# LTC6803.net
KiCad netlist of a schematic drawn in Altium Designer
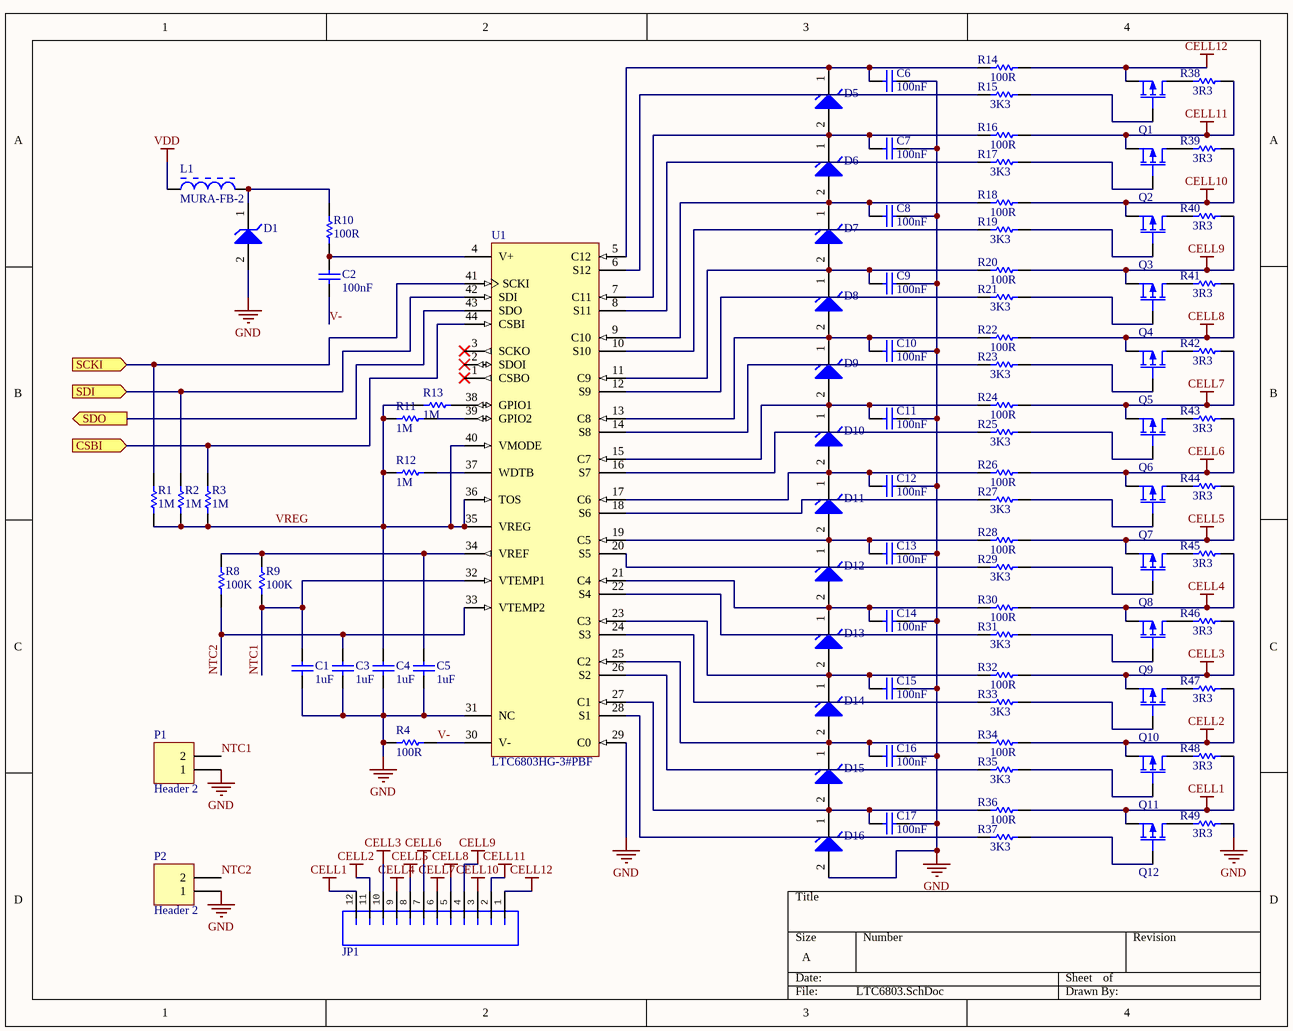
[diagram p0: LTC6803.SchDoc]

(export (version "E")
  (design (tool "Eeschema 10.0.6"))
  (components
    (comp (ref "C1")
      (value "1uF")
      (footprint "CAPC0603(1608)100_N")
      (description "CAP 1uF 6.3V Â±10% 0603 (1608 Metric) Thickness 1mm SMD")
      (fields (field (name "TOLERANCE") "Â±10%"))
      (libsource (lib "Altium Content Vault") (part "CAP"))
    )
    (comp (ref "C2")
      (value "100nF")
      (footprint "CAPC0603(1608)100_L")
      (description "CAP 100nF 100V Â±10% 0603 (1608 Metric) Thickness 1mm SMD")
      (fields (field (name "TOLERANCE") "Â±10%"))
      (libsource (lib "Altium Content Vault") (part "CAP"))
    )
    (comp (ref "C3")
      (value "1uF")
      (footprint "CAPC0603(1608)100_N")
      (description "CAP 1uF 6.3V Â±10% 0603 (1608 Metric) Thickness 1mm SMD")
      (fields (field (name "TOLERANCE") "Â±10%"))
      (libsource (lib "Altium Content Vault") (part "CAP"))
    )
    (comp (ref "C4")
      (value "1uF")
      (footprint "CAPC0603(1608)100_N")
      (description "CAP 1uF 6.3V Â±10% 0603 (1608 Metric) Thickness 1mm SMD")
      (fields (field (name "TOLERANCE") "Â±10%"))
      (libsource (lib "Altium Content Vault") (part "CAP"))
    )
    (comp (ref "C5")
      (value "1uF")
      (footprint "CAPC0603(1608)100_N")
      (description "CAP 1uF 6.3V Â±10% 0603 (1608 Metric) Thickness 1mm SMD")
      (fields (field (name "TOLERANCE") "Â±10%"))
      (libsource (lib "Altium Content Vault") (part "CAP"))
    )
    (comp (ref "C6")
      (value "100nF")
      (footprint "CAPC0603(1608)100_M")
      (description "CAP 100nF 6.3V Â±5% 0603 (1608 Metric) Thickness 1mm SMD")
      (fields (field (name "TOLERANCE") "Â±5%"))
      (libsource (lib "Altium Content Vault") (part "CAP"))
    )
    (comp (ref "C7")
      (value "100nF")
      (footprint "CAPC0603(1608)100_M")
      (description "CAP 100nF 6.3V Â±5% 0603 (1608 Metric) Thickness 1mm SMD")
      (fields (field (name "TOLERANCE") "Â±5%"))
      (libsource (lib "Altium Content Vault") (part "CAP"))
    )
    (comp (ref "C8")
      (value "100nF")
      (footprint "CAPC0603(1608)100_M")
      (description "CAP 100nF 6.3V Â±5% 0603 (1608 Metric) Thickness 1mm SMD")
      (fields (field (name "TOLERANCE") "Â±5%"))
      (libsource (lib "Altium Content Vault") (part "CAP"))
    )
    (comp (ref "C9")
      (value "100nF")
      (footprint "CAPC0603(1608)100_M")
      (description "CAP 100nF 6.3V Â±5% 0603 (1608 Metric) Thickness 1mm SMD")
      (fields (field (name "TOLERANCE") "Â±5%"))
      (libsource (lib "Altium Content Vault") (part "CAP"))
    )
    (comp (ref "C10")
      (value "100nF")
      (footprint "CAPC0603(1608)100_M")
      (description "CAP 100nF 6.3V Â±5% 0603 (1608 Metric) Thickness 1mm SMD")
      (fields (field (name "TOLERANCE") "Â±5%"))
      (libsource (lib "Altium Content Vault") (part "CAP"))
    )
    (comp (ref "C11")
      (value "100nF")
      (footprint "CAPC0603(1608)100_M")
      (description "CAP 100nF 6.3V Â±5% 0603 (1608 Metric) Thickness 1mm SMD")
      (fields (field (name "TOLERANCE") "Â±5%"))
      (libsource (lib "Altium Content Vault") (part "CAP"))
    )
    (comp (ref "C12")
      (value "100nF")
      (footprint "CAPC0603(1608)100_M")
      (description "CAP 100nF 6.3V Â±5% 0603 (1608 Metric) Thickness 1mm SMD")
      (fields (field (name "TOLERANCE") "Â±5%"))
      (libsource (lib "Altium Content Vault") (part "CAP"))
    )
    (comp (ref "C13")
      (value "100nF")
      (footprint "CAPC0603(1608)100_M")
      (description "CAP 100nF 6.3V Â±5% 0603 (1608 Metric) Thickness 1mm SMD")
      (fields (field (name "TOLERANCE") "Â±5%"))
      (libsource (lib "Altium Content Vault") (part "CAP"))
    )
    (comp (ref "C14")
      (value "100nF")
      (footprint "CAPC0603(1608)100_M")
      (description "CAP 100nF 6.3V Â±5% 0603 (1608 Metric) Thickness 1mm SMD")
      (fields (field (name "TOLERANCE") "Â±5%"))
      (libsource (lib "Altium Content Vault") (part "CAP"))
    )
    (comp (ref "C15")
      (value "100nF")
      (footprint "CAPC0603(1608)100_M")
      (description "CAP 100nF 6.3V Â±5% 0603 (1608 Metric) Thickness 1mm SMD")
      (fields (field (name "TOLERANCE") "Â±5%"))
      (libsource (lib "Altium Content Vault") (part "CAP"))
    )
    (comp (ref "C16")
      (value "100nF")
      (footprint "CAPC0603(1608)100_M")
      (description "CAP 100nF 6.3V Â±5% 0603 (1608 Metric) Thickness 1mm SMD")
      (fields (field (name "TOLERANCE") "Â±5%"))
      (libsource (lib "Altium Content Vault") (part "CAP"))
    )
    (comp (ref "C17")
      (value "100nF")
      (footprint "CAPC0603(1608)100_M")
      (description "CAP 100nF 6.3V Â±5% 0603 (1608 Metric) Thickness 1mm SMD")
      (fields (field (name "TOLERANCE") "Â±5%"))
      (libsource (lib "Altium Content Vault") (part "CAP"))
    )
    (comp (ref "D1") (value "~") (footprint "SOD-123") (libsource (lib "Components") (part "CMHZ5265B")))
    (comp (ref "D5")
      (value "~")
      (footprint "ONSC-SOD-323-2-477-02_V")
      (description "Zener Voltage Regulator, 300 mW, 2-Pin SOD-323, Tape and Reel")
      (fields (field (name "MANUFACTURER") "On Semiconductor") (field (name "PARTNUMBER") "MM3Z12VT1"))
      (libsource (lib "Altium Content Vault") (part "ONSC-K1A2-2"))
    )
    (comp (ref "D6")
      (value "~")
      (footprint "ONSC-SOD-323-2-477-02_V")
      (description "Zener Voltage Regulator, 300 mW, 2-Pin SOD-323, Tape and Reel")
      (fields (field (name "MANUFACTURER") "On Semiconductor") (field (name "PARTNUMBER") "MM3Z12VT1"))
      (libsource (lib "Altium Content Vault") (part "ONSC-K1A2-2"))
    )
    (comp (ref "D7")
      (value "~")
      (footprint "ONSC-SOD-323-2-477-02_V")
      (description "Zener Voltage Regulator, 300 mW, 2-Pin SOD-323, Tape and Reel")
      (fields (field (name "MANUFACTURER") "On Semiconductor") (field (name "PARTNUMBER") "MM3Z12VT1"))
      (libsource (lib "Altium Content Vault") (part "ONSC-K1A2-2"))
    )
    (comp (ref "D8")
      (value "~")
      (footprint "ONSC-SOD-323-2-477-02_V")
      (description "Zener Voltage Regulator, 300 mW, 2-Pin SOD-323, Tape and Reel")
      (fields (field (name "MANUFACTURER") "On Semiconductor") (field (name "PARTNUMBER") "MM3Z12VT1"))
      (libsource (lib "Altium Content Vault") (part "ONSC-K1A2-2"))
    )
    (comp (ref "D9")
      (value "~")
      (footprint "ONSC-SOD-323-2-477-02_V")
      (description "Zener Voltage Regulator, 300 mW, 2-Pin SOD-323, Tape and Reel")
      (fields (field (name "MANUFACTURER") "On Semiconductor") (field (name "PARTNUMBER") "MM3Z12VT1"))
      (libsource (lib "Altium Content Vault") (part "ONSC-K1A2-2"))
    )
    (comp (ref "D10")
      (value "~")
      (footprint "ONSC-SOD-323-2-477-02_V")
      (description "Zener Voltage Regulator, 300 mW, 2-Pin SOD-323, Tape and Reel")
      (fields (field (name "MANUFACTURER") "On Semiconductor") (field (name "PARTNUMBER") "MM3Z12VT1"))
      (libsource (lib "Altium Content Vault") (part "ONSC-K1A2-2"))
    )
    (comp (ref "D11")
      (value "~")
      (footprint "ONSC-SOD-323-2-477-02_V")
      (description "Zener Voltage Regulator, 300 mW, 2-Pin SOD-323, Tape and Reel")
      (fields (field (name "MANUFACTURER") "On Semiconductor") (field (name "PARTNUMBER") "MM3Z12VT1"))
      (libsource (lib "Altium Content Vault") (part "ONSC-K1A2-2"))
    )
    (comp (ref "D12")
      (value "~")
      (footprint "ONSC-SOD-323-2-477-02_V")
      (description "Zener Voltage Regulator, 300 mW, 2-Pin SOD-323, Tape and Reel")
      (fields (field (name "MANUFACTURER") "On Semiconductor") (field (name "PARTNUMBER") "MM3Z12VT1"))
      (libsource (lib "Altium Content Vault") (part "ONSC-K1A2-2"))
    )
    (comp (ref "D13")
      (value "~")
      (footprint "ONSC-SOD-323-2-477-02_V")
      (description "Zener Voltage Regulator, 300 mW, 2-Pin SOD-323, Tape and Reel")
      (fields (field (name "MANUFACTURER") "On Semiconductor") (field (name "PARTNUMBER") "MM3Z12VT1"))
      (libsource (lib "Altium Content Vault") (part "ONSC-K1A2-2"))
    )
    (comp (ref "D14")
      (value "~")
      (footprint "ONSC-SOD-323-2-477-02_V")
      (description "Zener Voltage Regulator, 300 mW, 2-Pin SOD-323, Tape and Reel")
      (fields (field (name "MANUFACTURER") "On Semiconductor") (field (name "PARTNUMBER") "MM3Z12VT1"))
      (libsource (lib "Altium Content Vault") (part "ONSC-K1A2-2"))
    )
    (comp (ref "D15")
      (value "~")
      (footprint "ONSC-SOD-323-2-477-02_V")
      (description "Zener Voltage Regulator, 300 mW, 2-Pin SOD-323, Tape and Reel")
      (fields (field (name "MANUFACTURER") "On Semiconductor") (field (name "PARTNUMBER") "MM3Z12VT1"))
      (libsource (lib "Altium Content Vault") (part "ONSC-K1A2-2"))
    )
    (comp (ref "D16")
      (value "~")
      (footprint "ONSC-SOD-323-2-477-02_V")
      (description "Zener Voltage Regulator, 300 mW, 2-Pin SOD-323, Tape and Reel")
      (fields (field (name "MANUFACTURER") "On Semiconductor") (field (name "PARTNUMBER") "MM3Z12VT1"))
      (libsource (lib "Altium Content Vault") (part "ONSC-K1A2-2"))
    )
    (comp (ref "JP1")
      (value "~")
      (footprint "JST-12-PTH")
      (libsource (lib "Components") (part "JST_12_RIGHT"))
    )
    (comp (ref "L1")
      (value "MURA-FB-2")
      (footprint "MURA-BLM31-B60-CHIP-2_V1")
      (libsource (lib "Components") (part "MURA-FB-2"))
    )
    (comp (ref "P1")
      (value "Header 2")
      (footprint "HDR1X2")
      (description "Header, 2-Pin")
      (fields (field (name "PUBLISHER") "Altium Limited"))
      (libsource (lib "Miscellaneous Connectors") (part "Header 2"))
    )
    (comp (ref "P2")
      (value "Header 2")
      (footprint "HDR1X2")
      (description "Header, 2-Pin")
      (fields (field (name "PUBLISHER") "Altium Limited"))
      (libsource (lib "Miscellaneous Connectors") (part "Header 2"))
    )
    (comp (ref "Q1")
      (value "MOSFET-P")
      (footprint "SOT23-3")
      (description "P-Channel MOSFET")
      (fields (field (name "PUBLISHER") "Altium Limited"))
      (libsource (lib "Components") (part "MOSFET-P"))
    )
    (comp (ref "Q2")
      (value "MOSFET-P")
      (footprint "SOT23-3")
      (description "P-Channel MOSFET")
      (fields (field (name "PUBLISHER") "Altium Limited"))
      (libsource (lib "Components") (part "MOSFET-P"))
    )
    (comp (ref "Q3")
      (value "MOSFET-P")
      (footprint "SOT23-3")
      (description "P-Channel MOSFET")
      (fields (field (name "PUBLISHER") "Altium Limited"))
      (libsource (lib "Components") (part "MOSFET-P"))
    )
    (comp (ref "Q4")
      (value "MOSFET-P")
      (footprint "SOT23-3")
      (description "P-Channel MOSFET")
      (fields (field (name "PUBLISHER") "Altium Limited"))
      (libsource (lib "Components") (part "MOSFET-P"))
    )
    (comp (ref "Q5")
      (value "MOSFET-P")
      (footprint "SOT23-3")
      (description "P-Channel MOSFET")
      (fields (field (name "PUBLISHER") "Altium Limited"))
      (libsource (lib "Components") (part "MOSFET-P"))
    )
    (comp (ref "Q6")
      (value "MOSFET-P")
      (footprint "SOT23-3")
      (description "P-Channel MOSFET")
      (fields (field (name "PUBLISHER") "Altium Limited"))
      (libsource (lib "Components") (part "MOSFET-P"))
    )
    (comp (ref "Q7")
      (value "MOSFET-P")
      (footprint "SOT23-3")
      (description "P-Channel MOSFET")
      (fields (field (name "PUBLISHER") "Altium Limited"))
      (libsource (lib "Components") (part "MOSFET-P"))
    )
    (comp (ref "Q8")
      (value "MOSFET-P")
      (footprint "SOT23-3")
      (description "P-Channel MOSFET")
      (fields (field (name "PUBLISHER") "Altium Limited"))
      (libsource (lib "Components") (part "MOSFET-P"))
    )
    (comp (ref "Q9")
      (value "MOSFET-P")
      (footprint "SOT23-3")
      (description "P-Channel MOSFET")
      (fields (field (name "PUBLISHER") "Altium Limited"))
      (libsource (lib "Components") (part "MOSFET-P"))
    )
    (comp (ref "Q10")
      (value "MOSFET-P")
      (footprint "SOT23-3")
      (description "P-Channel MOSFET")
      (fields (field (name "PUBLISHER") "Altium Limited"))
      (libsource (lib "Components") (part "MOSFET-P"))
    )
    (comp (ref "Q11")
      (value "MOSFET-P")
      (footprint "SOT23-3")
      (description "P-Channel MOSFET")
      (fields (field (name "PUBLISHER") "Altium Limited"))
      (libsource (lib "Components") (part "MOSFET-P"))
    )
    (comp (ref "Q12")
      (value "MOSFET-P")
      (footprint "SOT23-3")
      (description "P-Channel MOSFET")
      (fields (field (name "PUBLISHER") "Altium Limited"))
      (libsource (lib "Components") (part "MOSFET-P"))
    )
    (comp (ref "R1")
      (value "1M")
      (footprint "RESC0603(1608)_L")
      (description "1M 0.1W 1% 0603 (1608 Metric)  SMD")
      (fields (field (name "POWER") "0.1 W") (field (name "TOLERANCE") "1 %"))
      (libsource (lib "Altium Content Vault") (part "RES"))
    )
    (comp (ref "R2")
      (value "1M")
      (footprint "RESC0603(1608)_L")
      (description "1M 0.1W 1% 0603 (1608 Metric)  SMD")
      (fields (field (name "POWER") "0.1 W") (field (name "TOLERANCE") "1 %"))
      (libsource (lib "Altium Content Vault") (part "RES"))
    )
    (comp (ref "R3")
      (value "1M")
      (footprint "RESC0603(1608)_L")
      (description "1M 0.1W 1% 0603 (1608 Metric)  SMD")
      (fields (field (name "POWER") "0.1 W") (field (name "TOLERANCE") "1 %"))
      (libsource (lib "Altium Content Vault") (part "RES"))
    )
    (comp (ref "R4")
      (value "100R")
      (footprint "RESC0603(1608)_L")
      (description "100R 0.1W 5% 0603 (1608 Metric)  SMD")
      (fields (field (name "TOLERANCE") "5 %") (field (name "POWER") "0.1 W"))
      (libsource (lib "Altium Content Vault") (part "RES"))
    )
    (comp (ref "R8")
      (value "100K")
      (footprint "RESC0603(1608)_N")
      (description "100K 0.1W 5% 0603 (1608 Metric)  SMD")
      (fields (field (name "TOLERANCE") "5 %") (field (name "POWER") "0.1 W"))
      (libsource (lib "Altium Content Vault") (part "RES"))
    )
    (comp (ref "R9")
      (value "100K")
      (footprint "RESC0603(1608)_N")
      (description "100K 0.1W 5% 0603 (1608 Metric)  SMD")
      (fields (field (name "TOLERANCE") "5 %") (field (name "POWER") "0.1 W"))
      (libsource (lib "Altium Content Vault") (part "RES"))
    )
    (comp (ref "R10")
      (value "100R")
      (footprint "RESC0603(1608)_L")
      (description "100R 0.1W 5% 0603 (1608 Metric)  SMD")
      (fields (field (name "TOLERANCE") "5 %") (field (name "POWER") "0.1 W"))
      (libsource (lib "Altium Content Vault") (part "CMP-1012-00050-1"))
    )
    (comp (ref "R11")
      (value "1M")
      (footprint "RESC0603(1608)_L")
      (description "1M 0.1W 1% 0603 (1608 Metric)  SMD")
      (fields (field (name "POWER") "0.1 W") (field (name "TOLERANCE") "1 %"))
      (libsource (lib "Altium Content Vault") (part "RES"))
    )
    (comp (ref "R12")
      (value "1M")
      (footprint "RESC0603(1608)_L")
      (description "1M 0.1W 1% 0603 (1608 Metric)  SMD")
      (fields (field (name "POWER") "0.1 W") (field (name "TOLERANCE") "1 %"))
      (libsource (lib "Altium Content Vault") (part "RES"))
    )
    (comp (ref "R13")
      (value "1M")
      (footprint "RESC0603(1608)_L")
      (description "1M 0.1W 1% 0603 (1608 Metric)  SMD")
      (fields (field (name "POWER") "0.1 W") (field (name "TOLERANCE") "1 %"))
      (libsource (lib "Altium Content Vault") (part "RES"))
    )
    (comp (ref "R14")
      (value "100R")
      (footprint "RESC0603(1608)_N")
      (description "100R 0.1W 5% 0603 (1608 Metric)  SMD")
      (fields (field (name "TOLERANCE") "5 %") (field (name "POWER") "0.1 W"))
      (libsource (lib "Altium Content Vault") (part "CMP-1012-00050-1"))
    )
    (comp (ref "R15")
      (value "3K3")
      (footprint "RESC0603(1608)_N")
      (description "3K3 0.1W 5% 0603 (1608 Metric)  SMD")
      (fields (field (name "TOLERANCE") "5 %") (field (name "POWER") "0.1 W"))
      (libsource (lib "Altium Content Vault") (part "RES"))
    )
    (comp (ref "R16")
      (value "100R")
      (footprint "RESC0603(1608)_N")
      (description "100R 0.1W 5% 0603 (1608 Metric)  SMD")
      (fields (field (name "TOLERANCE") "5 %") (field (name "POWER") "0.1 W"))
      (libsource (lib "Altium Content Vault") (part "CMP-1012-00050-1"))
    )
    (comp (ref "R17")
      (value "3K3")
      (footprint "RESC0603(1608)_N")
      (description "3K3 0.1W 5% 0603 (1608 Metric)  SMD")
      (fields (field (name "TOLERANCE") "5 %") (field (name "POWER") "0.1 W"))
      (libsource (lib "Altium Content Vault") (part "RES"))
    )
    (comp (ref "R18")
      (value "100R")
      (footprint "RESC0603(1608)_N")
      (description "100R 0.1W 5% 0603 (1608 Metric)  SMD")
      (fields (field (name "TOLERANCE") "5 %") (field (name "POWER") "0.1 W"))
      (libsource (lib "Altium Content Vault") (part "CMP-1012-00050-1"))
    )
    (comp (ref "R19")
      (value "3K3")
      (footprint "RESC0603(1608)_N")
      (description "3K3 0.1W 5% 0603 (1608 Metric)  SMD")
      (fields (field (name "TOLERANCE") "5 %") (field (name "POWER") "0.1 W"))
      (libsource (lib "Altium Content Vault") (part "RES"))
    )
    (comp (ref "R20")
      (value "100R")
      (footprint "RESC0603(1608)_N")
      (description "100R 0.1W 5% 0603 (1608 Metric)  SMD")
      (fields (field (name "TOLERANCE") "5 %") (field (name "POWER") "0.1 W"))
      (libsource (lib "Altium Content Vault") (part "CMP-1012-00050-1"))
    )
    (comp (ref "R21")
      (value "3K3")
      (footprint "RESC0603(1608)_N")
      (description "3K3 0.1W 5% 0603 (1608 Metric)  SMD")
      (fields (field (name "TOLERANCE") "5 %") (field (name "POWER") "0.1 W"))
      (libsource (lib "Altium Content Vault") (part "RES"))
    )
    (comp (ref "R22")
      (value "100R")
      (footprint "RESC0603(1608)_N")
      (description "100R 0.1W 5% 0603 (1608 Metric)  SMD")
      (fields (field (name "TOLERANCE") "5 %") (field (name "POWER") "0.1 W"))
      (libsource (lib "Altium Content Vault") (part "CMP-1012-00050-1"))
    )
    (comp (ref "R23")
      (value "3K3")
      (footprint "RESC0603(1608)_N")
      (description "3K3 0.1W 5% 0603 (1608 Metric)  SMD")
      (fields (field (name "TOLERANCE") "5 %") (field (name "POWER") "0.1 W"))
      (libsource (lib "Altium Content Vault") (part "RES"))
    )
    (comp (ref "R24")
      (value "100R")
      (footprint "RESC0603(1608)_N")
      (description "100R 0.1W 5% 0603 (1608 Metric)  SMD")
      (fields (field (name "TOLERANCE") "5 %") (field (name "POWER") "0.1 W"))
      (libsource (lib "Altium Content Vault") (part "CMP-1012-00050-1"))
    )
    (comp (ref "R25")
      (value "3K3")
      (footprint "RESC0603(1608)_N")
      (description "3K3 0.1W 5% 0603 (1608 Metric)  SMD")
      (fields (field (name "TOLERANCE") "5 %") (field (name "POWER") "0.1 W"))
      (libsource (lib "Altium Content Vault") (part "RES"))
    )
    (comp (ref "R26")
      (value "100R")
      (footprint "RESC0603(1608)_N")
      (description "100R 0.1W 5% 0603 (1608 Metric)  SMD")
      (fields (field (name "TOLERANCE") "5 %") (field (name "POWER") "0.1 W"))
      (libsource (lib "Altium Content Vault") (part "CMP-1012-00050-1"))
    )
    (comp (ref "R27")
      (value "3K3")
      (footprint "RESC0603(1608)_N")
      (description "3K3 0.1W 5% 0603 (1608 Metric)  SMD")
      (fields (field (name "TOLERANCE") "5 %") (field (name "POWER") "0.1 W"))
      (libsource (lib "Altium Content Vault") (part "RES"))
    )
    (comp (ref "R28")
      (value "100R")
      (footprint "RESC0603(1608)_N")
      (description "100R 0.1W 5% 0603 (1608 Metric)  SMD")
      (fields (field (name "TOLERANCE") "5 %") (field (name "POWER") "0.1 W"))
      (libsource (lib "Altium Content Vault") (part "CMP-1012-00050-1"))
    )
    (comp (ref "R29")
      (value "3K3")
      (footprint "RESC0603(1608)_N")
      (description "3K3 0.1W 5% 0603 (1608 Metric)  SMD")
      (fields (field (name "TOLERANCE") "5 %") (field (name "POWER") "0.1 W"))
      (libsource (lib "Altium Content Vault") (part "RES"))
    )
    (comp (ref "R30")
      (value "100R")
      (footprint "RESC0603(1608)_N")
      (description "100R 0.1W 5% 0603 (1608 Metric)  SMD")
      (fields (field (name "TOLERANCE") "5 %") (field (name "POWER") "0.1 W"))
      (libsource (lib "Altium Content Vault") (part "CMP-1012-00050-1"))
    )
    (comp (ref "R31")
      (value "3K3")
      (footprint "RESC0603(1608)_N")
      (description "3K3 0.1W 5% 0603 (1608 Metric)  SMD")
      (fields (field (name "TOLERANCE") "5 %") (field (name "POWER") "0.1 W"))
      (libsource (lib "Altium Content Vault") (part "RES"))
    )
    (comp (ref "R32")
      (value "100R")
      (footprint "RESC0603(1608)_N")
      (description "100R 0.1W 5% 0603 (1608 Metric)  SMD")
      (fields (field (name "TOLERANCE") "5 %") (field (name "POWER") "0.1 W"))
      (libsource (lib "Altium Content Vault") (part "CMP-1012-00050-1"))
    )
    (comp (ref "R33")
      (value "3K3")
      (footprint "RESC0603(1608)_N")
      (description "3K3 0.1W 5% 0603 (1608 Metric)  SMD")
      (fields (field (name "TOLERANCE") "5 %") (field (name "POWER") "0.1 W"))
      (libsource (lib "Altium Content Vault") (part "RES"))
    )
    (comp (ref "R34")
      (value "100R")
      (footprint "RESC0603(1608)_N")
      (description "100R 0.1W 5% 0603 (1608 Metric)  SMD")
      (fields (field (name "TOLERANCE") "5 %") (field (name "POWER") "0.1 W"))
      (libsource (lib "Altium Content Vault") (part "CMP-1012-00050-1"))
    )
    (comp (ref "R35")
      (value "3K3")
      (footprint "RESC0603(1608)_N")
      (description "3K3 0.1W 5% 0603 (1608 Metric)  SMD")
      (fields (field (name "TOLERANCE") "5 %") (field (name "POWER") "0.1 W"))
      (libsource (lib "Altium Content Vault") (part "RES"))
    )
    (comp (ref "R36")
      (value "100R")
      (footprint "RESC0603(1608)_N")
      (description "100R 0.1W 5% 0603 (1608 Metric)  SMD")
      (fields (field (name "TOLERANCE") "5 %") (field (name "POWER") "0.1 W"))
      (libsource (lib "Altium Content Vault") (part "CMP-1012-00050-1"))
    )
    (comp (ref "R37")
      (value "3K3")
      (footprint "RESC0603(1608)_N")
      (description "3K3 0.1W 5% 0603 (1608 Metric)  SMD")
      (fields (field (name "TOLERANCE") "5 %") (field (name "POWER") "0.1 W"))
      (libsource (lib "Altium Content Vault") (part "RES"))
    )
    (comp (ref "R38")
      (value "3R3")
      (footprint "RESC2512(6432)_N")
      (description "3R3 1W 5% 2512 (6432 Metric)  SMD")
      (fields (field (name "TOLERANCE") "5 %") (field (name "POWER") "1 W"))
      (libsource (lib "Altium Content Vault") (part "RES"))
    )
    (comp (ref "R39")
      (value "3R3")
      (footprint "RESC2512(6432)_N")
      (description "3R3 1W 5% 2512 (6432 Metric)  SMD")
      (fields (field (name "TOLERANCE") "5 %") (field (name "POWER") "1 W"))
      (libsource (lib "Altium Content Vault") (part "RES"))
    )
    (comp (ref "R40")
      (value "3R3")
      (footprint "RESC2512(6432)_N")
      (description "3R3 1W 5% 2512 (6432 Metric)  SMD")
      (fields (field (name "TOLERANCE") "5 %") (field (name "POWER") "1 W"))
      (libsource (lib "Altium Content Vault") (part "RES"))
    )
    (comp (ref "R41")
      (value "3R3")
      (footprint "RESC2512(6432)_N")
      (description "3R3 1W 5% 2512 (6432 Metric)  SMD")
      (fields (field (name "TOLERANCE") "5 %") (field (name "POWER") "1 W"))
      (libsource (lib "Altium Content Vault") (part "RES"))
    )
    (comp (ref "R42")
      (value "3R3")
      (footprint "RESC2512(6432)_N")
      (description "3R3 1W 5% 2512 (6432 Metric)  SMD")
      (fields (field (name "TOLERANCE") "5 %") (field (name "POWER") "1 W"))
      (libsource (lib "Altium Content Vault") (part "RES"))
    )
    (comp (ref "R43")
      (value "3R3")
      (footprint "RESC2512(6432)_N")
      (description "3R3 1W 5% 2512 (6432 Metric)  SMD")
      (fields (field (name "TOLERANCE") "5 %") (field (name "POWER") "1 W"))
      (libsource (lib "Altium Content Vault") (part "RES"))
    )
    (comp (ref "R44")
      (value "3R3")
      (footprint "RESC2512(6432)_N")
      (description "3R3 1W 5% 2512 (6432 Metric)  SMD")
      (fields (field (name "TOLERANCE") "5 %") (field (name "POWER") "1 W"))
      (libsource (lib "Altium Content Vault") (part "RES"))
    )
    (comp (ref "R45")
      (value "3R3")
      (footprint "RESC2512(6432)_N")
      (description "3R3 1W 5% 2512 (6432 Metric)  SMD")
      (fields (field (name "TOLERANCE") "5 %") (field (name "POWER") "1 W"))
      (libsource (lib "Altium Content Vault") (part "RES"))
    )
    (comp (ref "R46")
      (value "3R3")
      (footprint "RESC2512(6432)_N")
      (description "3R3 1W 5% 2512 (6432 Metric)  SMD")
      (fields (field (name "TOLERANCE") "5 %") (field (name "POWER") "1 W"))
      (libsource (lib "Altium Content Vault") (part "RES"))
    )
    (comp (ref "R47")
      (value "3R3")
      (footprint "RESC2512(6432)_N")
      (description "3R3 1W 5% 2512 (6432 Metric)  SMD")
      (fields (field (name "TOLERANCE") "5 %") (field (name "POWER") "1 W"))
      (libsource (lib "Altium Content Vault") (part "RES"))
    )
    (comp (ref "R48")
      (value "3R3")
      (footprint "RESC2512(6432)_N")
      (description "3R3 1W 5% 2512 (6432 Metric)  SMD")
      (fields (field (name "TOLERANCE") "5 %") (field (name "POWER") "1 W"))
      (libsource (lib "Altium Content Vault") (part "RES"))
    )
    (comp (ref "R49")
      (value "3R3")
      (footprint "RESC2512(6432)_N")
      (description "3R3 1W 5% 2512 (6432 Metric)  SMD")
      (fields (field (name "TOLERANCE") "5 %") (field (name "POWER") "1 W"))
      (libsource (lib "Altium Content Vault") (part "RES"))
    )
    (comp (ref "U1")
      (value "LTC6803HG-3#PBF")
      (footprint "LT-G-44_L")
      (description "Multicell Battery Stack Monitor, 60 V Vin MAX, 44-pin SOP (G-44), -40 to 125 degC, Pb-Free")
      (fields (field (name "MANUFACTURER") "Linear Technology"))
      (libsource (lib "Altium Content Vault") (part "LT-LTC6803-3-G-44"))
    )
  )
  (nets
    (net (code "1") (name "/CSBI") (class "Default")
      (node (ref "R3") (pin "2") (pinfunction "2_2") (pintype "passive"))
      (node (ref "U1") (pin "44") (pinfunction "CSBI_44") (pintype "input"))
    )
    (net (code "2") (name "/NTC1") (class "Default")
      (node (ref "C1") (pin "2") (pinfunction "2_2") (pintype "passive"))
      (node (ref "P1") (pin "2") (pinfunction "2_2") (pintype "passive"))
      (node (ref "R9") (pin "1") (pinfunction "1_1") (pintype "passive"))
      (node (ref "U1") (pin "32") (pinfunction "VTEMP1_32") (pintype "input"))
    )
    (net (code "3") (name "/NTC2") (class "Default")
      (node (ref "C3") (pin "2") (pinfunction "2_2") (pintype "passive"))
      (node (ref "P2") (pin "2") (pinfunction "2_2") (pintype "passive"))
      (node (ref "R8") (pin "1") (pinfunction "1_1") (pintype "passive"))
      (node (ref "U1") (pin "33") (pinfunction "VTEMP2_33") (pintype "input"))
    )
    (net (code "4") (name "/SCKI") (class "Default")
      (node (ref "R1") (pin "2") (pinfunction "2_2") (pintype "passive"))
      (node (ref "U1") (pin "41") (pinfunction "SCKI_41") (pintype "input"))
    )
    (net (code "5") (name "/SDI") (class "Default")
      (node (ref "R2") (pin "2") (pinfunction "2_2") (pintype "passive"))
      (node (ref "U1") (pin "42") (pinfunction "SDI_42") (pintype "input"))
    )
    (net (code "6") (name "/SDO") (class "Default")
      (node (ref "U1") (pin "43") (pinfunction "SDO_43") (pintype "open_collector"))
    )
    (net (code "7") (name "/V-") (class "Default")
      (node (ref "C2") (pin "1") (pinfunction "1_1") (pintype "passive"))
      (node (ref "R4") (pin "2") (pinfunction "2_2") (pintype "passive"))
      (node (ref "U1") (pin "30") (pinfunction "V-_30") (pintype "power_in"))
    )
    (net (code "8") (name "/VREG") (class "Default")
      (node (ref "C4") (pin "2") (pinfunction "2_2") (pintype "passive"))
      (node (ref "R1") (pin "1") (pinfunction "1_1") (pintype "passive"))
      (node (ref "R11") (pin "1") (pinfunction "1_1") (pintype "passive"))
      (node (ref "R12") (pin "1") (pinfunction "1_1") (pintype "passive"))
      (node (ref "R13") (pin "1") (pinfunction "1_1") (pintype "passive"))
      (node (ref "R2") (pin "1") (pinfunction "1_1") (pintype "passive"))
      (node (ref "R3") (pin "1") (pinfunction "1_1") (pintype "passive"))
      (node (ref "U1") (pin "35") (pinfunction "VREG_35") (pintype "power_in"))
      (node (ref "U1") (pin "36") (pinfunction "TOS_36") (pintype "input"))
      (node (ref "U1") (pin "40") (pinfunction "VMODE_40") (pintype "input"))
    )
    (net (code "9") (name "CELL1") (class "Default")
      (node (ref "JP1") (pin "12") (pinfunction "12_12") (pintype "passive"))
      (node (ref "Q12") (pin "3") (pinfunction "S_3") (pintype "passive"))
      (node (ref "R36") (pin "2") (pinfunction "2_2") (pintype "passive"))
      (node (ref "R48") (pin "1") (pinfunction "1_1") (pintype "passive"))
    )
    (net (code "10") (name "CELL2") (class "Default")
      (node (ref "JP1") (pin "11") (pinfunction "11_11") (pintype "passive"))
      (node (ref "Q11") (pin "3") (pinfunction "S_3") (pintype "passive"))
      (node (ref "R34") (pin "2") (pinfunction "2_2") (pintype "passive"))
      (node (ref "R47") (pin "1") (pinfunction "1_1") (pintype "passive"))
    )
    (net (code "11") (name "CELL3") (class "Default")
      (node (ref "JP1") (pin "10") (pinfunction "10_10") (pintype "passive"))
      (node (ref "Q10") (pin "3") (pinfunction "S_3") (pintype "passive"))
      (node (ref "R32") (pin "2") (pinfunction "2_2") (pintype "passive"))
      (node (ref "R46") (pin "1") (pinfunction "1_1") (pintype "passive"))
    )
    (net (code "12") (name "CELL4") (class "Default")
      (node (ref "JP1") (pin "9") (pinfunction "9_9") (pintype "passive"))
      (node (ref "Q9") (pin "3") (pinfunction "S_3") (pintype "passive"))
      (node (ref "R30") (pin "2") (pinfunction "2_2") (pintype "passive"))
      (node (ref "R45") (pin "1") (pinfunction "1_1") (pintype "passive"))
    )
    (net (code "13") (name "CELL5") (class "Default")
      (node (ref "JP1") (pin "8") (pinfunction "8_8") (pintype "passive"))
      (node (ref "Q8") (pin "3") (pinfunction "S_3") (pintype "passive"))
      (node (ref "R28") (pin "2") (pinfunction "2_2") (pintype "passive"))
      (node (ref "R44") (pin "1") (pinfunction "1_1") (pintype "passive"))
    )
    (net (code "14") (name "CELL6") (class "Default")
      (node (ref "JP1") (pin "7") (pinfunction "7_7") (pintype "passive"))
      (node (ref "Q7") (pin "3") (pinfunction "S_3") (pintype "passive"))
      (node (ref "R26") (pin "2") (pinfunction "2_2") (pintype "passive"))
      (node (ref "R43") (pin "1") (pinfunction "1_1") (pintype "passive"))
    )
    (net (code "15") (name "CELL7") (class "Default")
      (node (ref "JP1") (pin "6") (pinfunction "6_6") (pintype "passive"))
      (node (ref "Q6") (pin "3") (pinfunction "S_3") (pintype "passive"))
      (node (ref "R24") (pin "2") (pinfunction "2_2") (pintype "passive"))
      (node (ref "R42") (pin "1") (pinfunction "1_1") (pintype "passive"))
    )
    (net (code "16") (name "CELL8") (class "Default")
      (node (ref "JP1") (pin "5") (pinfunction "5_5") (pintype "passive"))
      (node (ref "Q5") (pin "3") (pinfunction "S_3") (pintype "passive"))
      (node (ref "R22") (pin "2") (pinfunction "2_2") (pintype "passive"))
      (node (ref "R41") (pin "1") (pinfunction "1_1") (pintype "passive"))
    )
    (net (code "17") (name "CELL9") (class "Default")
      (node (ref "JP1") (pin "4") (pinfunction "4_4") (pintype "passive"))
      (node (ref "Q4") (pin "3") (pinfunction "S_3") (pintype "passive"))
      (node (ref "R20") (pin "2") (pinfunction "2_2") (pintype "passive"))
      (node (ref "R40") (pin "1") (pinfunction "1_1") (pintype "passive"))
    )
    (net (code "18") (name "CELL10") (class "Default")
      (node (ref "JP1") (pin "3") (pinfunction "3_3") (pintype "passive"))
      (node (ref "Q3") (pin "3") (pinfunction "S_3") (pintype "passive"))
      (node (ref "R18") (pin "2") (pinfunction "2_2") (pintype "passive"))
      (node (ref "R39") (pin "1") (pinfunction "1_1") (pintype "passive"))
    )
    (net (code "19") (name "CELL11") (class "Default")
      (node (ref "JP1") (pin "2") (pinfunction "2_2") (pintype "passive"))
      (node (ref "Q2") (pin "3") (pinfunction "S_3") (pintype "passive"))
      (node (ref "R16") (pin "2") (pinfunction "2_2") (pintype "passive"))
      (node (ref "R38") (pin "1") (pinfunction "1_1") (pintype "passive"))
    )
    (net (code "20") (name "CELL12") (class "Default")
      (node (ref "JP1") (pin "1") (pinfunction "1_1") (pintype "passive"))
      (node (ref "Q1") (pin "3") (pinfunction "S_3") (pintype "passive"))
      (node (ref "R14") (pin "2") (pinfunction "2_2") (pintype "passive"))
    )
    (net (code "21") (name "GND") (class "Default")
      (node (ref "C1") (pin "1") (pinfunction "1_1") (pintype "passive"))
      (node (ref "C10") (pin "1") (pinfunction "1_1") (pintype "passive"))
      (node (ref "C11") (pin "1") (pinfunction "1_1") (pintype "passive"))
      (node (ref "C12") (pin "1") (pinfunction "1_1") (pintype "passive"))
      (node (ref "C13") (pin "1") (pinfunction "1_1") (pintype "passive"))
      (node (ref "C14") (pin "1") (pinfunction "1_1") (pintype "passive"))
      (node (ref "C15") (pin "1") (pinfunction "1_1") (pintype "passive"))
      (node (ref "C16") (pin "1") (pinfunction "1_1") (pintype "passive"))
      (node (ref "C17") (pin "1") (pinfunction "1_1") (pintype "passive"))
      (node (ref "C3") (pin "1") (pinfunction "1_1") (pintype "passive"))
      (node (ref "C4") (pin "1") (pinfunction "1_1") (pintype "passive"))
      (node (ref "C5") (pin "1") (pinfunction "1_1") (pintype "passive"))
      (node (ref "C6") (pin "1") (pinfunction "1_1") (pintype "passive"))
      (node (ref "C7") (pin "1") (pinfunction "1_1") (pintype "passive"))
      (node (ref "C8") (pin "1") (pinfunction "1_1") (pintype "passive"))
      (node (ref "C9") (pin "1") (pinfunction "1_1") (pintype "passive"))
      (node (ref "D1") (pin "2") (pinfunction "A_2") (pintype "passive"))
      (node (ref "D16") (pin "2") (pinfunction "A_2") (pintype "passive"))
      (node (ref "P1") (pin "1") (pinfunction "1_1") (pintype "passive"))
      (node (ref "P2") (pin "1") (pinfunction "1_1") (pintype "passive"))
      (node (ref "R4") (pin "1") (pinfunction "1_1") (pintype "passive"))
      (node (ref "R49") (pin "1") (pinfunction "1_1") (pintype "passive"))
      (node (ref "U1") (pin "29") (pinfunction "C0_29") (pintype "input"))
      (node (ref "U1") (pin "31") (pinfunction "NC_31") (pintype "passive"))
    )
    (net (code "22") (name "Net-(D1-K)") (class "Default")
      (node (ref "D1") (pin "1") (pinfunction "K_1") (pintype "passive"))
      (node (ref "L1") (pin "2") (pinfunction "2_2") (pintype "passive"))
      (node (ref "R10") (pin "2") (pinfunction "2_2") (pintype "passive"))
    )
    (net (code "23") (name "Net-(D5-A)") (class "Default")
      (node (ref "C7") (pin "2") (pinfunction "2_2") (pintype "passive"))
      (node (ref "D5") (pin "2") (pinfunction "A_2") (pintype "passive"))
      (node (ref "D6") (pin "1") (pinfunction "K_1") (pintype "passive"))
      (node (ref "R16") (pin "1") (pinfunction "1_1") (pintype "passive"))
      (node (ref "U1") (pin "7") (pinfunction "C11_7") (pintype "input"))
    )
    (net (code "24") (name "Net-(D5-K)") (class "Default")
      (node (ref "C6") (pin "2") (pinfunction "2_2") (pintype "passive"))
      (node (ref "D5") (pin "1") (pinfunction "K_1") (pintype "passive"))
      (node (ref "R14") (pin "1") (pinfunction "1_1") (pintype "passive"))
      (node (ref "U1") (pin "5") (pinfunction "C12_5") (pintype "input"))
    )
    (net (code "25") (name "Net-(D6-A)") (class "Default")
      (node (ref "C8") (pin "2") (pinfunction "2_2") (pintype "passive"))
      (node (ref "D6") (pin "2") (pinfunction "A_2") (pintype "passive"))
      (node (ref "D7") (pin "1") (pinfunction "K_1") (pintype "passive"))
      (node (ref "R18") (pin "1") (pinfunction "1_1") (pintype "passive"))
      (node (ref "U1") (pin "9") (pinfunction "C10_9") (pintype "input"))
    )
    (net (code "26") (name "Net-(D7-A)") (class "Default")
      (node (ref "C9") (pin "2") (pinfunction "2_2") (pintype "passive"))
      (node (ref "D7") (pin "2") (pinfunction "A_2") (pintype "passive"))
      (node (ref "D8") (pin "1") (pinfunction "K_1") (pintype "passive"))
      (node (ref "R20") (pin "1") (pinfunction "1_1") (pintype "passive"))
      (node (ref "U1") (pin "11") (pinfunction "C9_11") (pintype "input"))
    )
    (net (code "27") (name "Net-(D8-A)") (class "Default")
      (node (ref "C10") (pin "2") (pinfunction "2_2") (pintype "passive"))
      (node (ref "D8") (pin "2") (pinfunction "A_2") (pintype "passive"))
      (node (ref "D9") (pin "1") (pinfunction "K_1") (pintype "passive"))
      (node (ref "R22") (pin "1") (pinfunction "1_1") (pintype "passive"))
      (node (ref "U1") (pin "13") (pinfunction "C8_13") (pintype "input"))
    )
    (net (code "28") (name "Net-(D10-A)") (class "Default")
      (node (ref "C12") (pin "2") (pinfunction "2_2") (pintype "passive"))
      (node (ref "D10") (pin "2") (pinfunction "A_2") (pintype "passive"))
      (node (ref "D11") (pin "1") (pinfunction "K_1") (pintype "passive"))
      (node (ref "R26") (pin "1") (pinfunction "1_1") (pintype "passive"))
      (node (ref "U1") (pin "17") (pinfunction "C6_17") (pintype "input"))
    )
    (net (code "29") (name "Net-(D10-K)") (class "Default")
      (node (ref "C11") (pin "2") (pinfunction "2_2") (pintype "passive"))
      (node (ref "D10") (pin "1") (pinfunction "K_1") (pintype "passive"))
      (node (ref "D9") (pin "2") (pinfunction "A_2") (pintype "passive"))
      (node (ref "R24") (pin "1") (pinfunction "1_1") (pintype "passive"))
      (node (ref "U1") (pin "15") (pinfunction "C7_15") (pintype "input"))
    )
    (net (code "30") (name "Net-(D11-A)") (class "Default")
      (node (ref "C13") (pin "2") (pinfunction "2_2") (pintype "passive"))
      (node (ref "D11") (pin "2") (pinfunction "A_2") (pintype "passive"))
      (node (ref "D12") (pin "1") (pinfunction "K_1") (pintype "passive"))
      (node (ref "R28") (pin "1") (pinfunction "1_1") (pintype "passive"))
      (node (ref "U1") (pin "19") (pinfunction "C5_19") (pintype "input"))
    )
    (net (code "31") (name "Net-(D12-A)") (class "Default")
      (node (ref "C14") (pin "2") (pinfunction "2_2") (pintype "passive"))
      (node (ref "D12") (pin "2") (pinfunction "A_2") (pintype "passive"))
      (node (ref "D13") (pin "1") (pinfunction "K_1") (pintype "passive"))
      (node (ref "R30") (pin "1") (pinfunction "1_1") (pintype "passive"))
      (node (ref "U1") (pin "21") (pinfunction "C4_21") (pintype "input"))
    )
    (net (code "32") (name "Net-(D13-A)") (class "Default")
      (node (ref "C15") (pin "2") (pinfunction "2_2") (pintype "passive"))
      (node (ref "D13") (pin "2") (pinfunction "A_2") (pintype "passive"))
      (node (ref "D14") (pin "1") (pinfunction "K_1") (pintype "passive"))
      (node (ref "R32") (pin "1") (pinfunction "1_1") (pintype "passive"))
      (node (ref "U1") (pin "23") (pinfunction "C3_23") (pintype "input"))
    )
    (net (code "33") (name "Net-(D14-A)") (class "Default")
      (node (ref "C16") (pin "2") (pinfunction "2_2") (pintype "passive"))
      (node (ref "D14") (pin "2") (pinfunction "A_2") (pintype "passive"))
      (node (ref "D15") (pin "1") (pinfunction "K_1") (pintype "passive"))
      (node (ref "R34") (pin "1") (pinfunction "1_1") (pintype "passive"))
      (node (ref "U1") (pin "25") (pinfunction "C2_25") (pintype "input"))
    )
    (net (code "34") (name "Net-(D15-A)") (class "Default")
      (node (ref "C17") (pin "2") (pinfunction "2_2") (pintype "passive"))
      (node (ref "D15") (pin "2") (pinfunction "A_2") (pintype "passive"))
      (node (ref "D16") (pin "1") (pinfunction "K_1") (pintype "passive"))
      (node (ref "R36") (pin "1") (pinfunction "1_1") (pintype "passive"))
      (node (ref "U1") (pin "27") (pinfunction "C1_27") (pintype "input"))
    )
    (net (code "35") (name "Net-(Q1-D)") (class "Default")
      (node (ref "Q1") (pin "2") (pinfunction "D_2") (pintype "passive"))
      (node (ref "R38") (pin "2") (pinfunction "2_2") (pintype "passive"))
    )
    (net (code "36") (name "Net-(Q1-G)") (class "Default")
      (node (ref "Q1") (pin "1") (pinfunction "G_1") (pintype "passive"))
      (node (ref "R15") (pin "2") (pinfunction "2_2") (pintype "passive"))
    )
    (net (code "37") (name "Net-(Q2-D)") (class "Default")
      (node (ref "Q2") (pin "2") (pinfunction "D_2") (pintype "passive"))
      (node (ref "R39") (pin "2") (pinfunction "2_2") (pintype "passive"))
    )
    (net (code "38") (name "Net-(Q2-G)") (class "Default")
      (node (ref "Q2") (pin "1") (pinfunction "G_1") (pintype "passive"))
      (node (ref "R17") (pin "2") (pinfunction "2_2") (pintype "passive"))
    )
    (net (code "39") (name "Net-(Q3-D)") (class "Default")
      (node (ref "Q3") (pin "2") (pinfunction "D_2") (pintype "passive"))
      (node (ref "R40") (pin "2") (pinfunction "2_2") (pintype "passive"))
    )
    (net (code "40") (name "Net-(Q3-G)") (class "Default")
      (node (ref "Q3") (pin "1") (pinfunction "G_1") (pintype "passive"))
      (node (ref "R19") (pin "2") (pinfunction "2_2") (pintype "passive"))
    )
    (net (code "41") (name "Net-(Q4-D)") (class "Default")
      (node (ref "Q4") (pin "2") (pinfunction "D_2") (pintype "passive"))
      (node (ref "R41") (pin "2") (pinfunction "2_2") (pintype "passive"))
    )
    (net (code "42") (name "Net-(Q4-G)") (class "Default")
      (node (ref "Q4") (pin "1") (pinfunction "G_1") (pintype "passive"))
      (node (ref "R21") (pin "2") (pinfunction "2_2") (pintype "passive"))
    )
    (net (code "43") (name "Net-(Q5-D)") (class "Default")
      (node (ref "Q5") (pin "2") (pinfunction "D_2") (pintype "passive"))
      (node (ref "R42") (pin "2") (pinfunction "2_2") (pintype "passive"))
    )
    (net (code "44") (name "Net-(Q5-G)") (class "Default")
      (node (ref "Q5") (pin "1") (pinfunction "G_1") (pintype "passive"))
      (node (ref "R23") (pin "2") (pinfunction "2_2") (pintype "passive"))
    )
    (net (code "45") (name "Net-(Q6-D)") (class "Default")
      (node (ref "Q6") (pin "2") (pinfunction "D_2") (pintype "passive"))
      (node (ref "R43") (pin "2") (pinfunction "2_2") (pintype "passive"))
    )
    (net (code "46") (name "Net-(Q6-G)") (class "Default")
      (node (ref "Q6") (pin "1") (pinfunction "G_1") (pintype "passive"))
      (node (ref "R25") (pin "2") (pinfunction "2_2") (pintype "passive"))
    )
    (net (code "47") (name "Net-(Q7-D)") (class "Default")
      (node (ref "Q7") (pin "2") (pinfunction "D_2") (pintype "passive"))
      (node (ref "R44") (pin "2") (pinfunction "2_2") (pintype "passive"))
    )
    (net (code "48") (name "Net-(Q7-G)") (class "Default")
      (node (ref "Q7") (pin "1") (pinfunction "G_1") (pintype "passive"))
      (node (ref "R27") (pin "2") (pinfunction "2_2") (pintype "passive"))
    )
    (net (code "49") (name "Net-(Q8-D)") (class "Default")
      (node (ref "Q8") (pin "2") (pinfunction "D_2") (pintype "passive"))
      (node (ref "R45") (pin "2") (pinfunction "2_2") (pintype "passive"))
    )
    (net (code "50") (name "Net-(Q8-G)") (class "Default")
      (node (ref "Q8") (pin "1") (pinfunction "G_1") (pintype "passive"))
      (node (ref "R29") (pin "2") (pinfunction "2_2") (pintype "passive"))
    )
    (net (code "51") (name "Net-(Q9-D)") (class "Default")
      (node (ref "Q9") (pin "2") (pinfunction "D_2") (pintype "passive"))
      (node (ref "R46") (pin "2") (pinfunction "2_2") (pintype "passive"))
    )
    (net (code "52") (name "Net-(Q9-G)") (class "Default")
      (node (ref "Q9") (pin "1") (pinfunction "G_1") (pintype "passive"))
      (node (ref "R31") (pin "2") (pinfunction "2_2") (pintype "passive"))
    )
    (net (code "53") (name "Net-(Q10-D)") (class "Default")
      (node (ref "Q10") (pin "2") (pinfunction "D_2") (pintype "passive"))
      (node (ref "R47") (pin "2") (pinfunction "2_2") (pintype "passive"))
    )
    (net (code "54") (name "Net-(Q10-G)") (class "Default")
      (node (ref "Q10") (pin "1") (pinfunction "G_1") (pintype "passive"))
      (node (ref "R33") (pin "2") (pinfunction "2_2") (pintype "passive"))
    )
    (net (code "55") (name "Net-(Q11-D)") (class "Default")
      (node (ref "Q11") (pin "2") (pinfunction "D_2") (pintype "passive"))
      (node (ref "R48") (pin "2") (pinfunction "2_2") (pintype "passive"))
    )
    (net (code "56") (name "Net-(Q11-G)") (class "Default")
      (node (ref "Q11") (pin "1") (pinfunction "G_1") (pintype "passive"))
      (node (ref "R35") (pin "2") (pinfunction "2_2") (pintype "passive"))
    )
    (net (code "57") (name "Net-(Q12-D)") (class "Default")
      (node (ref "Q12") (pin "2") (pinfunction "D_2") (pintype "passive"))
      (node (ref "R49") (pin "2") (pinfunction "2_2") (pintype "passive"))
    )
    (net (code "58") (name "Net-(Q12-G)") (class "Default")
      (node (ref "Q12") (pin "1") (pinfunction "G_1") (pintype "passive"))
      (node (ref "R37") (pin "2") (pinfunction "2_2") (pintype "passive"))
    )
    (net (code "59") (name "Net-(U1-GPIO1)") (class "Default")
      (node (ref "R13") (pin "2") (pinfunction "2_2") (pintype "passive"))
      (node (ref "U1") (pin "38") (pinfunction "GPIO1_38") (pintype "bidirectional"))
    )
    (net (code "60") (name "Net-(U1-GPIO2)") (class "Default")
      (node (ref "R11") (pin "2") (pinfunction "2_2") (pintype "passive"))
      (node (ref "U1") (pin "39") (pinfunction "GPIO2_39") (pintype "bidirectional"))
    )
    (net (code "61") (name "Net-(U1-S1)") (class "Default")
      (node (ref "R37") (pin "1") (pinfunction "1_1") (pintype "passive"))
      (node (ref "U1") (pin "28") (pinfunction "S1_28") (pintype "tri_state"))
    )
    (net (code "62") (name "Net-(U1-S2)") (class "Default")
      (node (ref "R35") (pin "1") (pinfunction "1_1") (pintype "passive"))
      (node (ref "U1") (pin "26") (pinfunction "S2_26") (pintype "tri_state"))
    )
    (net (code "63") (name "Net-(U1-S3)") (class "Default")
      (node (ref "R33") (pin "1") (pinfunction "1_1") (pintype "passive"))
      (node (ref "U1") (pin "24") (pinfunction "S3_24") (pintype "tri_state"))
    )
    (net (code "64") (name "Net-(U1-S4)") (class "Default")
      (node (ref "R31") (pin "1") (pinfunction "1_1") (pintype "passive"))
      (node (ref "U1") (pin "22") (pinfunction "S4_22") (pintype "tri_state"))
    )
    (net (code "65") (name "Net-(U1-S5)") (class "Default")
      (node (ref "R29") (pin "1") (pinfunction "1_1") (pintype "passive"))
      (node (ref "U1") (pin "20") (pinfunction "S5_20") (pintype "tri_state"))
    )
    (net (code "66") (name "Net-(U1-S6)") (class "Default")
      (node (ref "R27") (pin "1") (pinfunction "1_1") (pintype "passive"))
      (node (ref "U1") (pin "18") (pinfunction "S6_18") (pintype "tri_state"))
    )
    (net (code "67") (name "Net-(U1-S7)") (class "Default")
      (node (ref "R25") (pin "1") (pinfunction "1_1") (pintype "passive"))
      (node (ref "U1") (pin "16") (pinfunction "S7_16") (pintype "tri_state"))
    )
    (net (code "68") (name "Net-(U1-S8)") (class "Default")
      (node (ref "R23") (pin "1") (pinfunction "1_1") (pintype "passive"))
      (node (ref "U1") (pin "14") (pinfunction "S8_14") (pintype "tri_state"))
    )
    (net (code "69") (name "Net-(U1-S9)") (class "Default")
      (node (ref "R21") (pin "1") (pinfunction "1_1") (pintype "passive"))
      (node (ref "U1") (pin "12") (pinfunction "S9_12") (pintype "tri_state"))
    )
    (net (code "70") (name "Net-(U1-S10)") (class "Default")
      (node (ref "R19") (pin "1") (pinfunction "1_1") (pintype "passive"))
      (node (ref "U1") (pin "10") (pinfunction "S10_10") (pintype "tri_state"))
    )
    (net (code "71") (name "Net-(U1-S11)") (class "Default")
      (node (ref "R17") (pin "1") (pinfunction "1_1") (pintype "passive"))
      (node (ref "U1") (pin "8") (pinfunction "S11_8") (pintype "tri_state"))
    )
    (net (code "72") (name "Net-(U1-S12)") (class "Default")
      (node (ref "R15") (pin "1") (pinfunction "1_1") (pintype "passive"))
      (node (ref "U1") (pin "6") (pinfunction "S12_6") (pintype "tri_state"))
    )
    (net (code "73") (name "Net-(U1-V+)") (class "Default")
      (node (ref "C2") (pin "2") (pinfunction "2_2") (pintype "passive"))
      (node (ref "R10") (pin "1") (pinfunction "1_1") (pintype "passive"))
      (node (ref "U1") (pin "4") (pinfunction "V+_4") (pintype "power_in"))
    )
    (net (code "74") (name "Net-(U1-VREF)") (class "Default")
      (node (ref "C5") (pin "2") (pinfunction "2_2") (pintype "passive"))
      (node (ref "R8") (pin "2") (pinfunction "2_2") (pintype "passive"))
      (node (ref "R9") (pin "2") (pinfunction "2_2") (pintype "passive"))
      (node (ref "U1") (pin "34") (pinfunction "VREF_34") (pintype "output"))
    )
    (net (code "75") (name "Net-(U1-WDTB)") (class "Default")
      (node (ref "R12") (pin "2") (pinfunction "2_2") (pintype "passive"))
      (node (ref "U1") (pin "37") (pinfunction "WDTB_37") (pintype "open_collector"))
    )
    (net (code "76") (name "VDD") (class "Default")
      (node (ref "L1") (pin "1") (pinfunction "1_1") (pintype "passive"))
    )
    (net (code "77") (name "unconnected-(U1-CSBO-Pad1)") (class "Default")
      (node (ref "U1") (pin "1") (pinfunction "CSBO_1") (pintype "output+no_connect"))
    )
    (net (code "78") (name "unconnected-(U1-SCKO-Pad3)") (class "Default")
      (node (ref "U1") (pin "3") (pinfunction "SCKO_3") (pintype "output+no_connect"))
    )
    (net (code "79") (name "unconnected-(U1-SDOI-Pad2)") (class "Default")
      (node (ref "U1") (pin "2") (pinfunction "SDOI_2") (pintype "bidirectional+no_connect"))
    )
  )
)
